# CONTROLLER.net
KiCad netlist of a schematic drawn in EAGLE
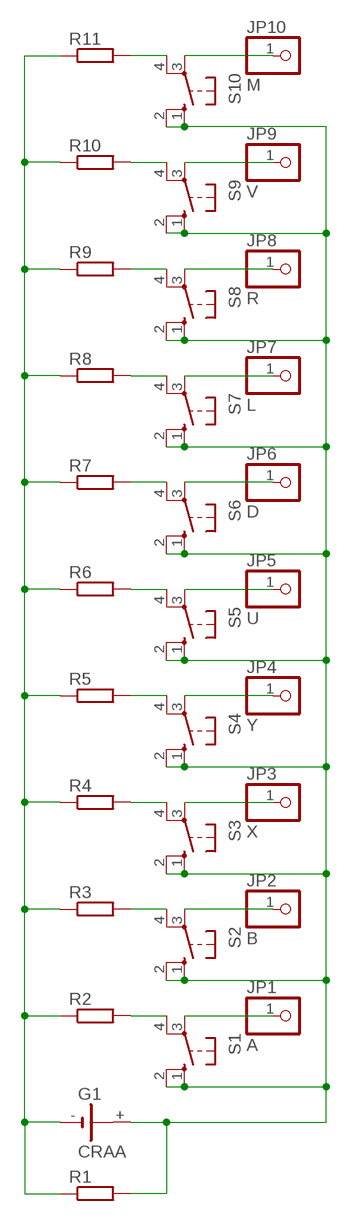
[diagram p0: schematic, sheet 1]

(export (version "E")
  (design (tool "Eeschema 10.0.6"))
  (components
    (comp (ref "G1")
      (value "CRAA")
      (footprint "eagle-import:CRAA")
      (libsource (lib "eagle-import") (part "CRAA"))
    )
    (comp (ref "JP1")
      (value "A")
      (footprint "eagle-import:1X01")
      (libsource (lib "eagle-import") (part "PINHD-1X1"))
    )
    (comp (ref "JP2")
      (value "B")
      (footprint "eagle-import:1X01")
      (libsource (lib "eagle-import") (part "PINHD-1X1"))
    )
    (comp (ref "JP3")
      (value "X")
      (footprint "eagle-import:1X01")
      (libsource (lib "eagle-import") (part "PINHD-1X1"))
    )
    (comp (ref "JP4")
      (value "Y")
      (footprint "eagle-import:1X01")
      (libsource (lib "eagle-import") (part "PINHD-1X1"))
    )
    (comp (ref "JP5")
      (value "U")
      (footprint "eagle-import:1X01")
      (libsource (lib "eagle-import") (part "PINHD-1X1"))
    )
    (comp (ref "JP6")
      (value "D")
      (footprint "eagle-import:1X01")
      (libsource (lib "eagle-import") (part "PINHD-1X1"))
    )
    (comp (ref "JP7")
      (value "L")
      (footprint "eagle-import:1X01")
      (libsource (lib "eagle-import") (part "PINHD-1X1"))
    )
    (comp (ref "JP8")
      (value "R")
      (footprint "eagle-import:1X01")
      (libsource (lib "eagle-import") (part "PINHD-1X1"))
    )
    (comp (ref "JP9")
      (value "V")
      (footprint "eagle-import:1X01")
      (libsource (lib "eagle-import") (part "PINHD-1X1"))
    )
    (comp (ref "JP10")
      (value "M")
      (footprint "eagle-import:1X01")
      (libsource (lib "eagle-import") (part "PINHD-1X1"))
    )
    (comp (ref "R1")
      (value "R-EU_0204/7")
      (footprint "eagle-import:0204_7")
      (libsource (lib "eagle-import") (part "R-EU_0204/7"))
    )
    (comp (ref "R2")
      (value "R-EU_0204/7")
      (footprint "eagle-import:0204_7")
      (libsource (lib "eagle-import") (part "R-EU_0204/7"))
    )
    (comp (ref "R3")
      (value "R-EU_0204/7")
      (footprint "eagle-import:0204_7")
      (libsource (lib "eagle-import") (part "R-EU_0204/7"))
    )
    (comp (ref "R4")
      (value "R-EU_0204/7")
      (footprint "eagle-import:0204_7")
      (libsource (lib "eagle-import") (part "R-EU_0204/7"))
    )
    (comp (ref "R5")
      (value "R-EU_0204/7")
      (footprint "eagle-import:0204_7")
      (libsource (lib "eagle-import") (part "R-EU_0204/7"))
    )
    (comp (ref "R6")
      (value "R-EU_0204/7")
      (footprint "eagle-import:0204_7")
      (libsource (lib "eagle-import") (part "R-EU_0204/7"))
    )
    (comp (ref "R7")
      (value "R-EU_0204/7")
      (footprint "eagle-import:0204_7")
      (libsource (lib "eagle-import") (part "R-EU_0204/7"))
    )
    (comp (ref "R8")
      (value "R-EU_0204/7")
      (footprint "eagle-import:0204_7")
      (libsource (lib "eagle-import") (part "R-EU_0204/7"))
    )
    (comp (ref "R9")
      (value "R-EU_0204/7")
      (footprint "eagle-import:0204_7")
      (libsource (lib "eagle-import") (part "R-EU_0204/7"))
    )
    (comp (ref "R10")
      (value "R-EU_0204/7")
      (footprint "eagle-import:0204_7")
      (libsource (lib "eagle-import") (part "R-EU_0204/7"))
    )
    (comp (ref "R11")
      (value "R-EU_0204/7")
      (footprint "eagle-import:0204_7")
      (libsource (lib "eagle-import") (part "R-EU_0204/7"))
    )
    (comp (ref "S1")
      (value "10-XX")
      (footprint "eagle-import:B3F-10XX")
      (fields (field (name "MPN") "B3F-1000"))
      (libsource (lib "eagle-import") (part "10-XX"))
    )
    (comp (ref "S2")
      (value "10-XX")
      (footprint "eagle-import:B3F-10XX")
      (fields (field (name "MPN") "B3F-1000"))
      (libsource (lib "eagle-import") (part "10-XX"))
    )
    (comp (ref "S3")
      (value "10-XX")
      (footprint "eagle-import:B3F-10XX")
      (fields (field (name "MPN") "B3F-1000"))
      (libsource (lib "eagle-import") (part "10-XX"))
    )
    (comp (ref "S4")
      (value "10-XX")
      (footprint "eagle-import:B3F-10XX")
      (fields (field (name "MPN") "B3F-1000"))
      (libsource (lib "eagle-import") (part "10-XX"))
    )
    (comp (ref "S5")
      (value "10-XX")
      (footprint "eagle-import:B3F-10XX")
      (fields (field (name "MPN") "B3F-1000"))
      (libsource (lib "eagle-import") (part "10-XX"))
    )
    (comp (ref "S6")
      (value "10-XX")
      (footprint "eagle-import:B3F-10XX")
      (fields (field (name "MPN") "B3F-1000"))
      (libsource (lib "eagle-import") (part "10-XX"))
    )
    (comp (ref "S7")
      (value "10-XX")
      (footprint "eagle-import:B3F-10XX")
      (fields (field (name "MPN") "B3F-1000"))
      (libsource (lib "eagle-import") (part "10-XX"))
    )
    (comp (ref "S8")
      (value "10-XX")
      (footprint "eagle-import:B3F-10XX")
      (fields (field (name "MPN") "B3F-1000"))
      (libsource (lib "eagle-import") (part "10-XX"))
    )
    (comp (ref "S9")
      (value "10-XX")
      (footprint "eagle-import:B3F-10XX")
      (fields (field (name "MPN") "B3F-1000"))
      (libsource (lib "eagle-import") (part "10-XX"))
    )
    (comp (ref "S10")
      (value "10-XX")
      (footprint "eagle-import:B3F-10XX")
      (fields (field (name "MPN") "B3F-1000"))
      (libsource (lib "eagle-import") (part "10-XX"))
    )
  )
  (nets
    (net (code "1") (name "Net-(G1-Pad-)") (class "Default")
      (node (ref "G1") (pin "-") (pinfunction "-_-") (pintype "passive"))
      (node (ref "R1") (pin "1") (pinfunction "1_1") (pintype "passive"))
      (node (ref "R10") (pin "1") (pinfunction "1_1") (pintype "passive"))
      (node (ref "R11") (pin "1") (pinfunction "1_1") (pintype "passive"))
      (node (ref "R2") (pin "1") (pinfunction "1_1") (pintype "passive"))
      (node (ref "R3") (pin "1") (pinfunction "1_1") (pintype "passive"))
      (node (ref "R4") (pin "1") (pinfunction "1_1") (pintype "passive"))
      (node (ref "R5") (pin "1") (pinfunction "1_1") (pintype "passive"))
      (node (ref "R6") (pin "1") (pinfunction "1_1") (pintype "passive"))
      (node (ref "R7") (pin "1") (pinfunction "1_1") (pintype "passive"))
      (node (ref "R8") (pin "1") (pinfunction "1_1") (pintype "passive"))
      (node (ref "R9") (pin "1") (pinfunction "1_1") (pintype "passive"))
    )
    (net (code "2") (name "Net-(S1-P)") (class "Default")
      (node (ref "JP1") (pin "1") (pinfunction "1_1") (pintype "passive"))
      (node (ref "S1") (pin "3") (pinfunction "P_3") (pintype "passive"))
    )
    (net (code "3") (name "Net-(S1-P1)") (class "Default")
      (node (ref "R2") (pin "2") (pinfunction "2_2") (pintype "passive"))
      (node (ref "S1") (pin "4") (pinfunction "P1_4") (pintype "passive"))
    )
    (net (code "4") (name "Net-(S1-S)") (class "Default")
      (node (ref "G1") (pin "+") (pinfunction "+_+") (pintype "passive"))
      (node (ref "R1") (pin "2") (pinfunction "2_2") (pintype "passive"))
      (node (ref "S1") (pin "1") (pinfunction "S_1") (pintype "passive"))
      (node (ref "S1") (pin "2") (pinfunction "S1_2") (pintype "passive"))
      (node (ref "S10") (pin "1") (pinfunction "S_1") (pintype "passive"))
      (node (ref "S10") (pin "2") (pinfunction "S1_2") (pintype "passive"))
      (node (ref "S2") (pin "1") (pinfunction "S_1") (pintype "passive"))
      (node (ref "S2") (pin "2") (pinfunction "S1_2") (pintype "passive"))
      (node (ref "S3") (pin "1") (pinfunction "S_1") (pintype "passive"))
      (node (ref "S3") (pin "2") (pinfunction "S1_2") (pintype "passive"))
      (node (ref "S4") (pin "1") (pinfunction "S_1") (pintype "passive"))
      (node (ref "S4") (pin "2") (pinfunction "S1_2") (pintype "passive"))
      (node (ref "S5") (pin "1") (pinfunction "S_1") (pintype "passive"))
      (node (ref "S5") (pin "2") (pinfunction "S1_2") (pintype "passive"))
      (node (ref "S6") (pin "1") (pinfunction "S_1") (pintype "passive"))
      (node (ref "S6") (pin "2") (pinfunction "S1_2") (pintype "passive"))
      (node (ref "S7") (pin "1") (pinfunction "S_1") (pintype "passive"))
      (node (ref "S7") (pin "2") (pinfunction "S1_2") (pintype "passive"))
      (node (ref "S8") (pin "1") (pinfunction "S_1") (pintype "passive"))
      (node (ref "S8") (pin "2") (pinfunction "S1_2") (pintype "passive"))
      (node (ref "S9") (pin "1") (pinfunction "S_1") (pintype "passive"))
      (node (ref "S9") (pin "2") (pinfunction "S1_2") (pintype "passive"))
    )
    (net (code "5") (name "Net-(S2-P)") (class "Default")
      (node (ref "JP2") (pin "1") (pinfunction "1_1") (pintype "passive"))
      (node (ref "S2") (pin "3") (pinfunction "P_3") (pintype "passive"))
    )
    (net (code "6") (name "Net-(S2-P1)") (class "Default")
      (node (ref "R3") (pin "2") (pinfunction "2_2") (pintype "passive"))
      (node (ref "S2") (pin "4") (pinfunction "P1_4") (pintype "passive"))
    )
    (net (code "7") (name "Net-(S3-P)") (class "Default")
      (node (ref "JP3") (pin "1") (pinfunction "1_1") (pintype "passive"))
      (node (ref "S3") (pin "3") (pinfunction "P_3") (pintype "passive"))
    )
    (net (code "8") (name "Net-(S3-P1)") (class "Default")
      (node (ref "R4") (pin "2") (pinfunction "2_2") (pintype "passive"))
      (node (ref "S3") (pin "4") (pinfunction "P1_4") (pintype "passive"))
    )
    (net (code "9") (name "Net-(S4-P)") (class "Default")
      (node (ref "JP4") (pin "1") (pinfunction "1_1") (pintype "passive"))
      (node (ref "S4") (pin "3") (pinfunction "P_3") (pintype "passive"))
    )
    (net (code "10") (name "Net-(S4-P1)") (class "Default")
      (node (ref "R5") (pin "2") (pinfunction "2_2") (pintype "passive"))
      (node (ref "S4") (pin "4") (pinfunction "P1_4") (pintype "passive"))
    )
    (net (code "11") (name "Net-(S5-P)") (class "Default")
      (node (ref "JP5") (pin "1") (pinfunction "1_1") (pintype "passive"))
      (node (ref "S5") (pin "3") (pinfunction "P_3") (pintype "passive"))
    )
    (net (code "12") (name "Net-(S5-P1)") (class "Default")
      (node (ref "R6") (pin "2") (pinfunction "2_2") (pintype "passive"))
      (node (ref "S5") (pin "4") (pinfunction "P1_4") (pintype "passive"))
    )
    (net (code "13") (name "Net-(S6-P)") (class "Default")
      (node (ref "JP6") (pin "1") (pinfunction "1_1") (pintype "passive"))
      (node (ref "S6") (pin "3") (pinfunction "P_3") (pintype "passive"))
    )
    (net (code "14") (name "Net-(S6-P1)") (class "Default")
      (node (ref "R7") (pin "2") (pinfunction "2_2") (pintype "passive"))
      (node (ref "S6") (pin "4") (pinfunction "P1_4") (pintype "passive"))
    )
    (net (code "15") (name "Net-(S7-P)") (class "Default")
      (node (ref "JP7") (pin "1") (pinfunction "1_1") (pintype "passive"))
      (node (ref "S7") (pin "3") (pinfunction "P_3") (pintype "passive"))
    )
    (net (code "16") (name "Net-(S7-P1)") (class "Default")
      (node (ref "R8") (pin "2") (pinfunction "2_2") (pintype "passive"))
      (node (ref "S7") (pin "4") (pinfunction "P1_4") (pintype "passive"))
    )
    (net (code "17") (name "Net-(S8-P)") (class "Default")
      (node (ref "JP8") (pin "1") (pinfunction "1_1") (pintype "passive"))
      (node (ref "S8") (pin "3") (pinfunction "P_3") (pintype "passive"))
    )
    (net (code "18") (name "Net-(S8-P1)") (class "Default")
      (node (ref "R9") (pin "2") (pinfunction "2_2") (pintype "passive"))
      (node (ref "S8") (pin "4") (pinfunction "P1_4") (pintype "passive"))
    )
    (net (code "19") (name "Net-(S9-P)") (class "Default")
      (node (ref "JP9") (pin "1") (pinfunction "1_1") (pintype "passive"))
      (node (ref "S9") (pin "3") (pinfunction "P_3") (pintype "passive"))
    )
    (net (code "20") (name "Net-(S9-P1)") (class "Default")
      (node (ref "R10") (pin "2") (pinfunction "2_2") (pintype "passive"))
      (node (ref "S9") (pin "4") (pinfunction "P1_4") (pintype "passive"))
    )
    (net (code "21") (name "Net-(S10-P)") (class "Default")
      (node (ref "JP10") (pin "1") (pinfunction "1_1") (pintype "passive"))
      (node (ref "S10") (pin "3") (pinfunction "P_3") (pintype "passive"))
    )
    (net (code "22") (name "Net-(S10-P1)") (class "Default")
      (node (ref "R11") (pin "2") (pinfunction "2_2") (pintype "passive"))
      (node (ref "S10") (pin "4") (pinfunction "P1_4") (pintype "passive"))
    )
    (net (code "23") (name "unconnected-(G1-+-Pad+@1)") (class "Default")
      (node (ref "G1") (pin "+@1") (pinfunction "+_+@1") (pintype "passive"))
    )
  )
)
